# Analog.net
KiCad netlist of a schematic drawn in Altium Designer
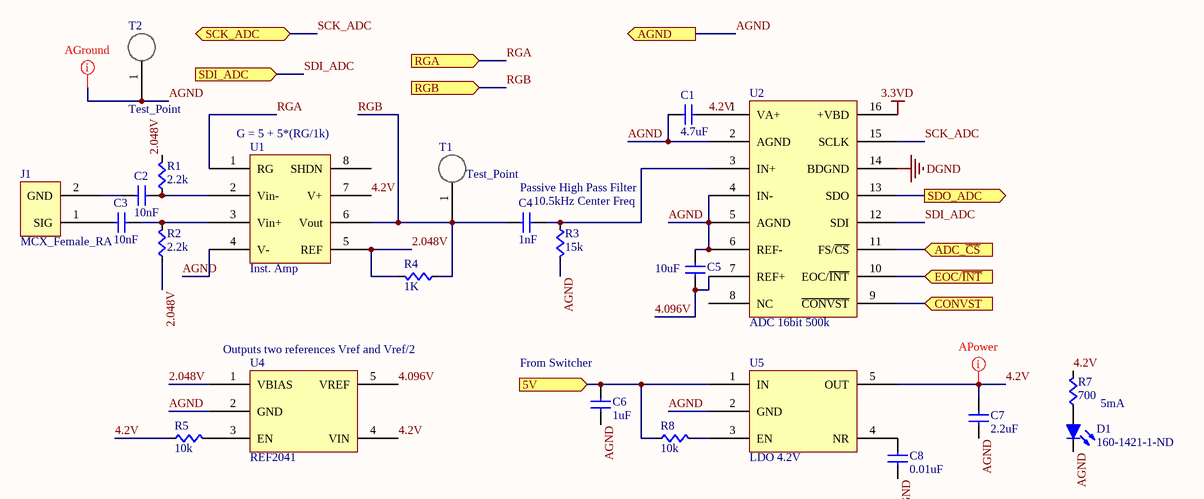
[diagram p0: Analog.SchDoc]

(export (version "E")
  (design (tool "Eeschema 10.0.6"))
  (components
    (comp (ref "C1")
      (value "4.7uF")
      (footprint "CAPC0603")
      (fields (field (name "Comment") "Cap"))
      (libsource (lib "SubjuGator8") (part "Cap"))
    )
    (comp (ref "C2")
      (value "10nF")
      (footprint "CAPC0603")
      (fields (field (name "Comment") "Cap"))
      (libsource (lib "SubjuGator8") (part "Cap"))
    )
    (comp (ref "C3")
      (value "10nF")
      (footprint "CAPC0603")
      (fields (field (name "Comment") "Cap"))
      (libsource (lib "SubjuGator8") (part "Cap"))
    )
    (comp (ref "C4")
      (value "1nF")
      (footprint "CAPC0603")
      (fields (field (name "Comment") "Cap"))
      (libsource (lib "SubjuGator8") (part "Cap"))
    )
    (comp (ref "C5")
      (value "10uF")
      (footprint "CAPC0603")
      (fields (field (name "Comment") "Cap"))
      (libsource (lib "SubjuGator8") (part "Cap"))
    )
    (comp (ref "C6")
      (value "1uF")
      (footprint "CAPC0603")
      (fields (field (name "Comment") "Cap"))
      (libsource (lib "SubjuGator8") (part "Cap"))
    )
    (comp (ref "C7")
      (value "2.2uF")
      (footprint "CAPC0603")
      (fields (field (name "Comment") "Cap"))
      (libsource (lib "SubjuGator8") (part "Cap"))
    )
    (comp (ref "C8")
      (value "0.01uF")
      (footprint "CAPC0603")
      (fields (field (name "Comment") "Cap"))
      (libsource (lib "SubjuGator8") (part "Cap"))
    )
    (comp (ref "D1")
      (value "LED-RED")
      (footprint "Hydrophone:LED0805-RED")
      (description "Light Emitting Diode - RED")
      (fields
        (field (name "MANUFACTURER PART NUMBER") "LTST-C171CKT")
        (field (name "MANUFACTURER") "Lite-On Inc")
        (field (name "SUPPLIER PART NUMBER") "160-1421-1-ND")
      )
      (libsource (lib "Hydrophone") (part "LED-RED"))
    )
    (comp (ref "J1")
      (value "MCX_Female_RA")
      (footprint "MCX_Female")
      (description "CONN MCX JACK R/A 50 OHM PCB")
      (libsource (lib "Hydrophone") (part "MCX_Female_RA"))
    )
    (comp (ref "R1")
      (value "2.2k")
      (footprint "RES0603")
      (fields (field (name "Comment") "Res"))
      (libsource (lib "SubjuGator8") (part "Res"))
    )
    (comp (ref "R2")
      (value "2.2k")
      (footprint "RES0603")
      (fields (field (name "Comment") "Res"))
      (libsource (lib "SubjuGator8") (part "Res"))
    )
    (comp (ref "R3")
      (value "15k")
      (footprint "RES0603")
      (fields (field (name "Comment") "Res"))
      (libsource (lib "SubjuGator8") (part "Res"))
    )
    (comp (ref "R4")
      (value "1K")
      (footprint "RES0603")
      (fields (field (name "Comment") "Res"))
      (libsource (lib "Passives") (part "Res"))
    )
    (comp (ref "R5")
      (value "10k")
      (footprint "RES0603")
      (fields (field (name "Comment") "Res"))
      (libsource (lib "SubjuGator8") (part "Res"))
    )
    (comp (ref "R7")
      (value "700")
      (footprint "RES0603")
      (fields (field (name "Comment") "Res"))
      (libsource (lib "SubjuGator8") (part "Res"))
    )
    (comp (ref "R8")
      (value "10k")
      (footprint "RES0603")
      (fields (field (name "Comment") "Res"))
      (libsource (lib "SubjuGator8") (part "Res"))
    )
    (comp (ref "T1")
      (value "Test_Point")
      (footprint "TP")
      (description "TEST POINT PC COMPACT .063\"D")
      (libsource (lib "Hydrophone") (part "Test_Point"))
    )
    (comp (ref "T2")
      (value "Test_Point")
      (footprint "TP")
      (description "TEST POINT PC COMPACT .063\"D")
      (libsource (lib "Hydrophone") (part "Test_Point"))
    )
    (comp (ref "U1")
      (value "Inst. Amp")
      (footprint "TSSOP-8n")
      (description "IC OPAMP INSTR 2MHZ RRO 8VSSOP")
      (libsource (lib "SubjuGator8") (part "INA331"))
    )
    (comp (ref "U2")
      (value "ADC 16bit 500k")
      (footprint "TSSOP-16pin")
      (description "IC ADC 16BIT 500KSPS 16-TSSOP")
      (libsource (lib "SubjuGator8") (part "ADC 16bit 500k"))
    )
    (comp (ref "U4")
      (value "REF2041")
      (footprint "SOT23-5")
      (description "IC VREF SERIES 2.05V/4.096V 5SOT")
      (libsource (lib "SubjuGator8") (part "REF2041"))
    )
    (comp (ref "U5")
      (value "LDO 4.2V")
      (footprint "sot23-5")
      (description "IC REG LDO 4.2V 0.2A 5SOT")
      (libsource (lib "SubjuGator8") (part "LDO 4.2V 200mA"))
    )
  )
  (nets
    (net (code "1") (name "/2.048V") (class "Default")
      (node (ref "R1") (pin "1") (pinfunction "A_1") (pintype "passive"))
      (node (ref "R2") (pin "2") (pinfunction "B_2") (pintype "passive"))
      (node (ref "R4") (pin "1") (pinfunction "A_1") (pintype "passive"))
      (node (ref "U1") (pin "5") (pinfunction "REF_5") (pintype "passive"))
      (node (ref "U4") (pin "1") (pinfunction "VBIAS_1") (pintype "passive"))
    )
    (net (code "2") (name "/4.2V") (class "Default")
      (node (ref "C1") (pin "2") (pinfunction "B_2") (pintype "passive"))
      (node (ref "C7") (pin "2") (pinfunction "B_2") (pintype "passive"))
      (node (ref "R5") (pin "2") (pinfunction "B_2") (pintype "passive"))
      (node (ref "R7") (pin "1") (pinfunction "A_1") (pintype "passive"))
      (node (ref "U1") (pin "7") (pinfunction "V+_7") (pintype "passive"))
      (node (ref "U2") (pin "1") (pinfunction "VA+_1") (pintype "passive"))
      (node (ref "U4") (pin "4") (pinfunction "VIN_4") (pintype "passive"))
      (node (ref "U5") (pin "5") (pinfunction "OUT_5") (pintype "passive"))
    )
    (net (code "3") (name "/4.096V") (class "Default")
      (node (ref "C5") (pin "2") (pinfunction "B_2") (pintype "passive"))
      (node (ref "U2") (pin "7") (pinfunction "REF+_7") (pintype "passive"))
      (node (ref "U4") (pin "5") (pinfunction "VREF_5") (pintype "passive"))
    )
    (net (code "4") (name "/5V") (class "Default")
      (node (ref "C6") (pin "2") (pinfunction "B_2") (pintype "passive"))
      (node (ref "R8") (pin "2") (pinfunction "B_2") (pintype "passive"))
      (node (ref "U5") (pin "1") (pinfunction "IN_1") (pintype "passive"))
    )
    (net (code "5") (name "/ADC_~{CS}") (class "Default")
      (node (ref "U2") (pin "11") (pinfunction "FS/~{CS}_11") (pintype "passive"))
    )
    (net (code "6") (name "/AGND") (class "Default")
      (node (ref "C1") (pin "1") (pinfunction "A_1") (pintype "passive"))
      (node (ref "C5") (pin "1") (pinfunction "A_1") (pintype "passive"))
      (node (ref "C6") (pin "1") (pinfunction "A_1") (pintype "passive"))
      (node (ref "C7") (pin "1") (pinfunction "A_1") (pintype "passive"))
      (node (ref "C8") (pin "1") (pinfunction "A_1") (pintype "passive"))
      (node (ref "D1") (pin "1") (pinfunction "K_1") (pintype "passive"))
      (node (ref "R3") (pin "1") (pinfunction "A_1") (pintype "passive"))
      (node (ref "T2") (pin "1") (pintype "passive"))
      (node (ref "U1") (pin "4") (pinfunction "V-_4") (pintype "passive"))
      (node (ref "U2") (pin "2") (pinfunction "AGND_2") (pintype "passive"))
      (node (ref "U2") (pin "4") (pinfunction "IN-_4") (pintype "passive"))
      (node (ref "U2") (pin "5") (pinfunction "AGND_5") (pintype "passive"))
      (node (ref "U2") (pin "6") (pinfunction "REF-_6") (pintype "passive"))
      (node (ref "U4") (pin "2") (pinfunction "GND_2") (pintype "passive"))
      (node (ref "U5") (pin "2") (pinfunction "GND_2") (pintype "passive"))
    )
    (net (code "7") (name "/CONVST") (class "Default")
      (node (ref "U2") (pin "9") (pinfunction "~{CONVST}_9") (pintype "passive"))
    )
    (net (code "8") (name "/EOC{slash}~{INT}") (class "Default")
      (node (ref "U2") (pin "10") (pinfunction "EOC/~{INT}_10") (pintype "passive"))
    )
    (net (code "9") (name "/RGA") (class "Default")
      (node (ref "U1") (pin "1") (pinfunction "RG_1") (pintype "passive"))
    )
    (net (code "10") (name "/RGB") (class "Default")
      (node (ref "C4") (pin "1") (pinfunction "A_1") (pintype "passive"))
      (node (ref "R4") (pin "2") (pinfunction "B_2") (pintype "passive"))
      (node (ref "T1") (pin "1") (pintype "passive"))
      (node (ref "U1") (pin "6") (pinfunction "Vout_6") (pintype "passive"))
    )
    (net (code "11") (name "/SCK_ADC") (class "Default")
      (node (ref "U2") (pin "15") (pinfunction "SCLK_15") (pintype "passive"))
    )
    (net (code "12") (name "/SDI_ADC") (class "Default")
      (node (ref "U2") (pin "12") (pinfunction "SDI_12") (pintype "passive"))
    )
    (net (code "13") (name "/SDO_ADC") (class "Default")
      (node (ref "U2") (pin "13") (pinfunction "SDO_13") (pintype "passive"))
    )
    (net (code "14") (name "3.3VD") (class "Default")
      (node (ref "U2") (pin "16") (pinfunction "+VBD_16") (pintype "passive"))
    )
    (net (code "15") (name "DGND") (class "Default")
      (node (ref "U2") (pin "14") (pinfunction "BDGND_14") (pintype "passive"))
    )
    (net (code "16") (name "Net-(C2-A)") (class "Default")
      (node (ref "C2") (pin "1") (pinfunction "A_1") (pintype "passive"))
      (node (ref "J1") (pin "2") (pinfunction "GND_2") (pintype "passive"))
    )
    (net (code "17") (name "Net-(C2-B)") (class "Default")
      (node (ref "C2") (pin "2") (pinfunction "B_2") (pintype "passive"))
      (node (ref "R1") (pin "2") (pinfunction "B_2") (pintype "passive"))
      (node (ref "U1") (pin "2") (pinfunction "Vin-_2") (pintype "passive"))
    )
    (net (code "18") (name "Net-(C3-A)") (class "Default")
      (node (ref "C3") (pin "1") (pinfunction "A_1") (pintype "passive"))
      (node (ref "J1") (pin "1") (pinfunction "SIG_1") (pintype "passive"))
    )
    (net (code "19") (name "Net-(C3-B)") (class "Default")
      (node (ref "C3") (pin "2") (pinfunction "B_2") (pintype "passive"))
      (node (ref "R2") (pin "1") (pinfunction "A_1") (pintype "passive"))
      (node (ref "U1") (pin "3") (pinfunction "Vin+_3") (pintype "passive"))
    )
    (net (code "20") (name "Net-(C4-B)") (class "Default")
      (node (ref "C4") (pin "2") (pinfunction "B_2") (pintype "passive"))
      (node (ref "R3") (pin "2") (pinfunction "B_2") (pintype "passive"))
      (node (ref "U2") (pin "3") (pinfunction "IN+_3") (pintype "passive"))
    )
    (net (code "21") (name "Net-(C8-B)") (class "Default")
      (node (ref "C8") (pin "2") (pinfunction "B_2") (pintype "passive"))
      (node (ref "U5") (pin "4") (pinfunction "NR_4") (pintype "passive"))
    )
    (net (code "22") (name "Net-(D1-A)") (class "Default")
      (node (ref "D1") (pin "2") (pinfunction "A_2") (pintype "passive"))
      (node (ref "R7") (pin "2") (pinfunction "B_2") (pintype "passive"))
    )
    (net (code "23") (name "Net-(R5-A)") (class "Default")
      (node (ref "R5") (pin "1") (pinfunction "A_1") (pintype "passive"))
      (node (ref "U4") (pin "3") (pinfunction "EN_3") (pintype "passive"))
    )
    (net (code "24") (name "Net-(R8-A)") (class "Default")
      (node (ref "R8") (pin "1") (pinfunction "A_1") (pintype "passive"))
      (node (ref "U5") (pin "3") (pinfunction "EN_3") (pintype "passive"))
    )
    (net (code "25") (name "unconnected-(U1-SHDN-Pad8)") (class "Default")
      (node (ref "U1") (pin "8") (pinfunction "SHDN_8") (pintype "passive"))
    )
    (net (code "26") (name "unconnected-(U2-NC-Pad8)") (class "Default")
      (node (ref "U2") (pin "8") (pinfunction "NC_8") (pintype "passive"))
    )
  )
)
